# cactusCup_v2.net
KiCad netlist of a schematic drawn in EAGLE
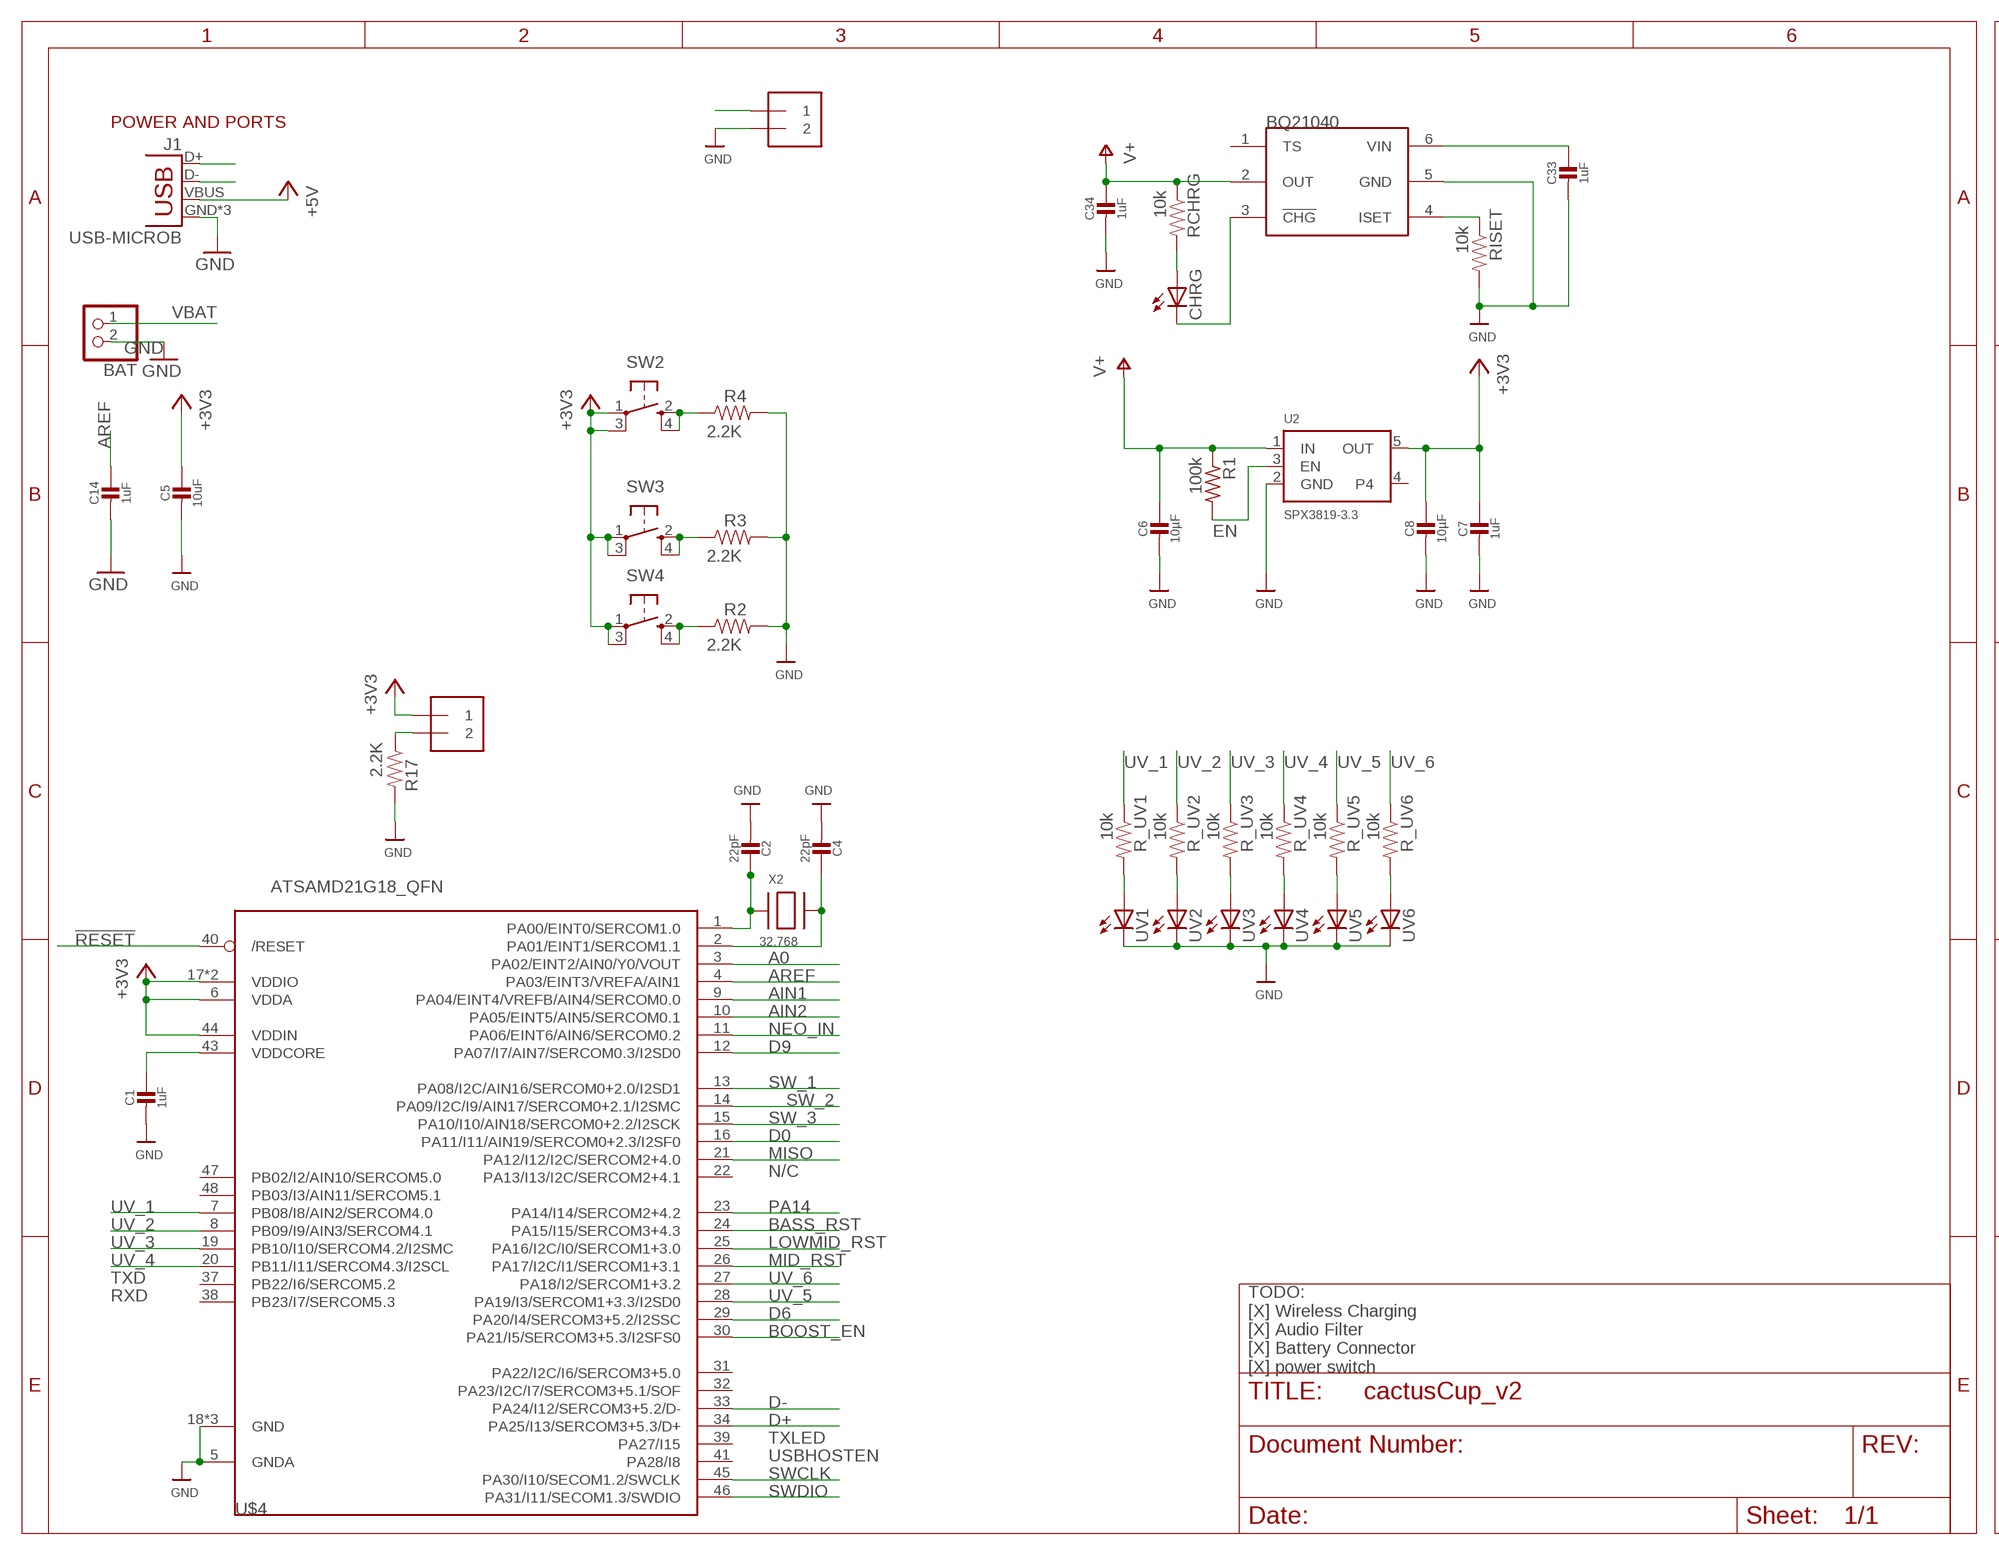
[diagram p0: schematic, sheet 1, part 1 of 2]
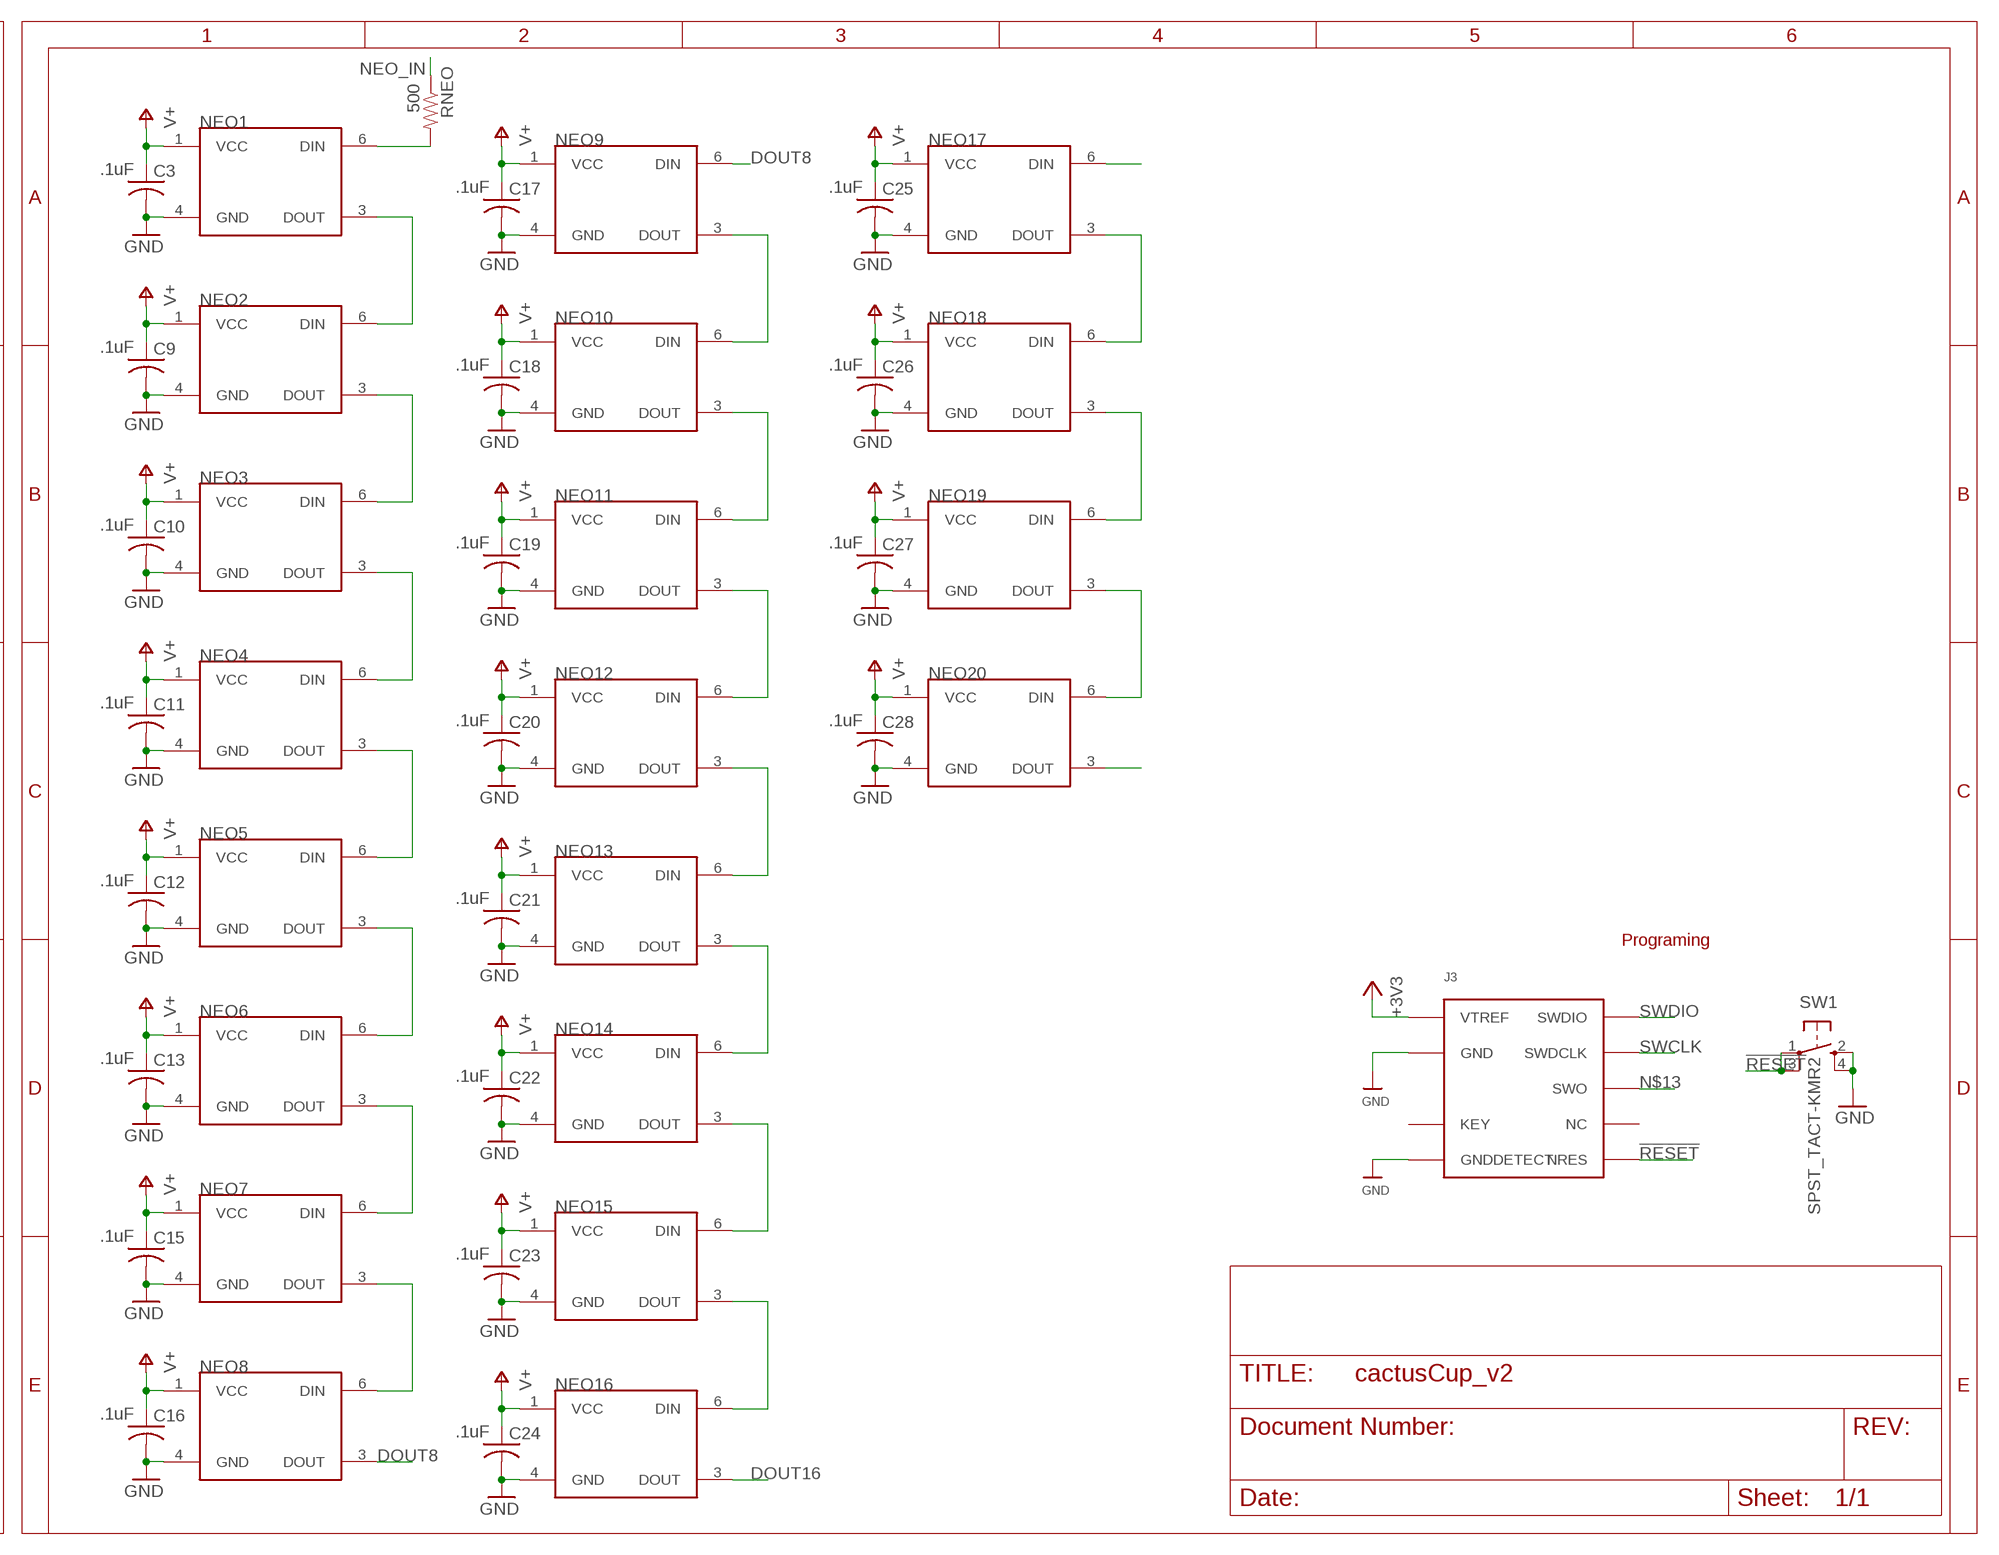
[diagram p1: schematic, sheet 1, part 2 of 2]

(export (version "E")
  (design (tool "Eeschema 10.0.6"))
  (components
    (comp (ref "BAT")
      (value "JST_2PIN-SMT-RA")
      (footprint "eagle-import:JST-PH-2-SMT-RA")
      (libsource (lib "eagle-import") (part "JST_2PIN-SMT-RA"))
    )
    (comp (ref "BQ21040")
      (value "BQ21040")
      (footprint "eagle-import:SOT23-6")
      (libsource (lib "eagle-import") (part "BQ21040"))
    )
    (comp (ref "C1")
      (value "1uF")
      (footprint "eagle-import:0603-NO")
      (libsource (lib "eagle-import") (part "CAP_CERAMIC0603_NO"))
    )
    (comp (ref "C2")
      (value "22pF")
      (footprint "eagle-import:0603-NO")
      (libsource (lib "eagle-import") (part "CAP_CERAMIC0603_NO"))
    )
    (comp (ref "C3")
      (value ".1uF")
      (footprint "eagle-import:C0603")
      (libsource (lib "eagle-import") (part "C-USC0603"))
    )
    (comp (ref "C4")
      (value "22pF")
      (footprint "eagle-import:0603-NO")
      (libsource (lib "eagle-import") (part "CAP_CERAMIC0603_NO"))
    )
    (comp (ref "C5")
      (value "10uF")
      (footprint "eagle-import:0805-NO")
      (libsource (lib "eagle-import") (part "CAP_CERAMIC0805-NOOUTLINE"))
    )
    (comp (ref "C6")
      (value "10µF")
      (footprint "eagle-import:0805-NO")
      (libsource (lib "eagle-import") (part "CAP_CERAMIC0805-NOOUTLINE"))
    )
    (comp (ref "C7")
      (value "1uF")
      (footprint "eagle-import:0603-NO")
      (libsource (lib "eagle-import") (part "CAP_CERAMIC0603_NO"))
    )
    (comp (ref "C8")
      (value "10µF")
      (footprint "eagle-import:0805-NO")
      (libsource (lib "eagle-import") (part "CAP_CERAMIC0805-NOOUTLINE"))
    )
    (comp (ref "C9")
      (value ".1uF")
      (footprint "eagle-import:C0603")
      (libsource (lib "eagle-import") (part "C-USC0603"))
    )
    (comp (ref "C10")
      (value ".1uF")
      (footprint "eagle-import:C0603")
      (libsource (lib "eagle-import") (part "C-USC0603"))
    )
    (comp (ref "C11")
      (value ".1uF")
      (footprint "eagle-import:C0603")
      (libsource (lib "eagle-import") (part "C-USC0603"))
    )
    (comp (ref "C12")
      (value ".1uF")
      (footprint "eagle-import:C0603")
      (libsource (lib "eagle-import") (part "C-USC0603"))
    )
    (comp (ref "C13")
      (value ".1uF")
      (footprint "eagle-import:C0603")
      (libsource (lib "eagle-import") (part "C-USC0603"))
    )
    (comp (ref "C14")
      (value "1uF")
      (footprint "eagle-import:0603-NO")
      (libsource (lib "eagle-import") (part "CAP_CERAMIC0603_NO"))
    )
    (comp (ref "C15")
      (value ".1uF")
      (footprint "eagle-import:C0603")
      (libsource (lib "eagle-import") (part "C-USC0603"))
    )
    (comp (ref "C16")
      (value ".1uF")
      (footprint "eagle-import:C0603")
      (libsource (lib "eagle-import") (part "C-USC0603"))
    )
    (comp (ref "C17")
      (value ".1uF")
      (footprint "eagle-import:C0603")
      (libsource (lib "eagle-import") (part "C-USC0603"))
    )
    (comp (ref "C18")
      (value ".1uF")
      (footprint "eagle-import:C0603")
      (libsource (lib "eagle-import") (part "C-USC0603"))
    )
    (comp (ref "C19")
      (value ".1uF")
      (footprint "eagle-import:C0603")
      (libsource (lib "eagle-import") (part "C-USC0603"))
    )
    (comp (ref "C20")
      (value ".1uF")
      (footprint "eagle-import:C0603")
      (libsource (lib "eagle-import") (part "C-USC0603"))
    )
    (comp (ref "C21")
      (value ".1uF")
      (footprint "eagle-import:C0603")
      (libsource (lib "eagle-import") (part "C-USC0603"))
    )
    (comp (ref "C22")
      (value ".1uF")
      (footprint "eagle-import:C0603")
      (libsource (lib "eagle-import") (part "C-USC0603"))
    )
    (comp (ref "C23")
      (value ".1uF")
      (footprint "eagle-import:C0603")
      (libsource (lib "eagle-import") (part "C-USC0603"))
    )
    (comp (ref "C24")
      (value ".1uF")
      (footprint "eagle-import:C0603")
      (libsource (lib "eagle-import") (part "C-USC0603"))
    )
    (comp (ref "C25")
      (value ".1uF")
      (footprint "eagle-import:C0603")
      (libsource (lib "eagle-import") (part "C-USC0603"))
    )
    (comp (ref "C26")
      (value ".1uF")
      (footprint "eagle-import:C0603")
      (libsource (lib "eagle-import") (part "C-USC0603"))
    )
    (comp (ref "C27")
      (value ".1uF")
      (footprint "eagle-import:C0603")
      (libsource (lib "eagle-import") (part "C-USC0603"))
    )
    (comp (ref "C28")
      (value ".1uF")
      (footprint "eagle-import:C0603")
      (libsource (lib "eagle-import") (part "C-USC0603"))
    )
    (comp (ref "C33")
      (value "1uF")
      (footprint "eagle-import:0603-NO")
      (libsource (lib "eagle-import") (part "CAP_CERAMIC0603_NO"))
    )
    (comp (ref "C34")
      (value "1uF")
      (footprint "eagle-import:0603-NO")
      (libsource (lib "eagle-import") (part "CAP_CERAMIC0603_NO"))
    )
    (comp (ref "CHRG")
      (value "LEDCHIPLED_0603")
      (footprint "eagle-import:CHIPLED_0603")
      (libsource (lib "eagle-import") (part "LEDCHIPLED_0603"))
    )
    (comp (ref "J1")
      (value "USB-MICROB")
      (footprint "eagle-import:USB-MICROB")
      (libsource (lib "eagle-import") (part "USB-MICROB"))
    )
    (comp (ref "J2")
      (value "1X2-3.5MM")
      (footprint "eagle-import:1X2-3.5MM")
      (libsource (lib "eagle-import") (part "1X2-3.5MM"))
    )
    (comp (ref "J3")
      (value "JLINK_10PIN")
      (footprint "eagle-import:FTSH-105-01-F-DH")
      (libsource (lib "eagle-import") (part "JLINK_10PIN"))
    )
    (comp (ref "J4")
      (value "1X2-3.5MM")
      (footprint "eagle-import:1X2-3.5MM")
      (libsource (lib "eagle-import") (part "1X2-3.5MM"))
    )
    (comp (ref "NEO1")
      (value "NEOPIXEL")
      (footprint "eagle-import:RGBLED5050")
      (libsource (lib "eagle-import") (part "NEOPIXEL"))
    )
    (comp (ref "NEO2")
      (value "NEOPIXEL")
      (footprint "eagle-import:RGBLED5050")
      (libsource (lib "eagle-import") (part "NEOPIXEL"))
    )
    (comp (ref "NEO3")
      (value "NEOPIXEL")
      (footprint "eagle-import:RGBLED5050")
      (libsource (lib "eagle-import") (part "NEOPIXEL"))
    )
    (comp (ref "NEO4")
      (value "NEOPIXEL")
      (footprint "eagle-import:RGBLED5050")
      (libsource (lib "eagle-import") (part "NEOPIXEL"))
    )
    (comp (ref "NEO5")
      (value "NEOPIXEL")
      (footprint "eagle-import:RGBLED5050")
      (libsource (lib "eagle-import") (part "NEOPIXEL"))
    )
    (comp (ref "NEO6")
      (value "NEOPIXEL")
      (footprint "eagle-import:RGBLED5050")
      (libsource (lib "eagle-import") (part "NEOPIXEL"))
    )
    (comp (ref "NEO7")
      (value "NEOPIXEL")
      (footprint "eagle-import:RGBLED5050")
      (libsource (lib "eagle-import") (part "NEOPIXEL"))
    )
    (comp (ref "NEO8")
      (value "NEOPIXEL")
      (footprint "eagle-import:RGBLED5050")
      (libsource (lib "eagle-import") (part "NEOPIXEL"))
    )
    (comp (ref "NEO9")
      (value "NEOPIXEL")
      (footprint "eagle-import:RGBLED5050")
      (libsource (lib "eagle-import") (part "NEOPIXEL"))
    )
    (comp (ref "NEO10")
      (value "NEOPIXEL")
      (footprint "eagle-import:RGBLED5050")
      (libsource (lib "eagle-import") (part "NEOPIXEL"))
    )
    (comp (ref "NEO11")
      (value "NEOPIXEL")
      (footprint "eagle-import:RGBLED5050")
      (libsource (lib "eagle-import") (part "NEOPIXEL"))
    )
    (comp (ref "NEO12")
      (value "NEOPIXEL")
      (footprint "eagle-import:RGBLED5050")
      (libsource (lib "eagle-import") (part "NEOPIXEL"))
    )
    (comp (ref "NEO13")
      (value "NEOPIXEL")
      (footprint "eagle-import:RGBLED5050")
      (libsource (lib "eagle-import") (part "NEOPIXEL"))
    )
    (comp (ref "NEO14")
      (value "NEOPIXEL")
      (footprint "eagle-import:RGBLED5050")
      (libsource (lib "eagle-import") (part "NEOPIXEL"))
    )
    (comp (ref "NEO15")
      (value "NEOPIXEL")
      (footprint "eagle-import:RGBLED5050")
      (libsource (lib "eagle-import") (part "NEOPIXEL"))
    )
    (comp (ref "NEO16")
      (value "NEOPIXEL")
      (footprint "eagle-import:RGBLED5050")
      (libsource (lib "eagle-import") (part "NEOPIXEL"))
    )
    (comp (ref "NEO17")
      (value "NEOPIXEL")
      (footprint "eagle-import:RGBLED5050")
      (libsource (lib "eagle-import") (part "NEOPIXEL"))
    )
    (comp (ref "NEO18")
      (value "NEOPIXEL")
      (footprint "eagle-import:RGBLED5050")
      (libsource (lib "eagle-import") (part "NEOPIXEL"))
    )
    (comp (ref "NEO19")
      (value "NEOPIXEL")
      (footprint "eagle-import:RGBLED5050")
      (libsource (lib "eagle-import") (part "NEOPIXEL"))
    )
    (comp (ref "NEO20")
      (value "NEOPIXEL")
      (footprint "eagle-import:RGBLED5050")
      (libsource (lib "eagle-import") (part "NEOPIXEL"))
    )
    (comp (ref "R1")
      (value "100k")
      (footprint "eagle-import:R0603")
      (libsource (lib "eagle-import") (part "R-US_R0603"))
    )
    (comp (ref "R2")
      (value "2.2K")
      (footprint "eagle-import:0603-RES")
      (libsource (lib "eagle-import") (part "0.27OHM-1/10W-1%(0603)"))
    )
    (comp (ref "R3")
      (value "2.2K")
      (footprint "eagle-import:0603-RES")
      (libsource (lib "eagle-import") (part "0.27OHM-1/10W-1%(0603)"))
    )
    (comp (ref "R4")
      (value "2.2K")
      (footprint "eagle-import:0603-RES")
      (libsource (lib "eagle-import") (part "0.27OHM-1/10W-1%(0603)"))
    )
    (comp (ref "R17")
      (value "2.2K")
      (footprint "eagle-import:0603-RES")
      (libsource (lib "eagle-import") (part "0.27OHM-1/10W-1%(0603)"))
    )
    (comp (ref "RCHRG")
      (value "10k")
      (footprint "eagle-import:0603-RES")
      (libsource (lib "eagle-import") (part "0.27OHM-1/10W-1%(0603)"))
    )
    (comp (ref "RISET")
      (value "10k")
      (footprint "eagle-import:0603-RES")
      (libsource (lib "eagle-import") (part "0.27OHM-1/10W-1%(0603)"))
    )
    (comp (ref "RNEO")
      (value "500")
      (footprint "eagle-import:0603-RES")
      (libsource (lib "eagle-import") (part "0.27OHM-1/10W-1%(0603)"))
    )
    (comp (ref "R_UV1")
      (value "10k")
      (footprint "eagle-import:0603-RES")
      (libsource (lib "eagle-import") (part "0.27OHM-1/10W-1%(0603)"))
    )
    (comp (ref "R_UV2")
      (value "10k")
      (footprint "eagle-import:0603-RES")
      (libsource (lib "eagle-import") (part "0.27OHM-1/10W-1%(0603)"))
    )
    (comp (ref "R_UV3")
      (value "10k")
      (footprint "eagle-import:0603-RES")
      (libsource (lib "eagle-import") (part "0.27OHM-1/10W-1%(0603)"))
    )
    (comp (ref "R_UV4")
      (value "10k")
      (footprint "eagle-import:0603-RES")
      (libsource (lib "eagle-import") (part "0.27OHM-1/10W-1%(0603)"))
    )
    (comp (ref "R_UV5")
      (value "10k")
      (footprint "eagle-import:0603-RES")
      (libsource (lib "eagle-import") (part "0.27OHM-1/10W-1%(0603)"))
    )
    (comp (ref "R_UV6")
      (value "10k")
      (footprint "eagle-import:0603-RES")
      (libsource (lib "eagle-import") (part "0.27OHM-1/10W-1%(0603)"))
    )
    (comp (ref "SW1")
      (value "SPST_TACT-KMR2")
      (footprint "eagle-import:KMR2")
      (libsource (lib "eagle-import") (part "SPST_TACT-KMR2"))
    )
    (comp (ref "SW2")
      (value "SPST_TACT-KMR2")
      (footprint "eagle-import:KMR2")
      (libsource (lib "eagle-import") (part "SPST_TACT-KMR2"))
    )
    (comp (ref "SW3")
      (value "SPST_TACT-KMR2")
      (footprint "eagle-import:KMR2")
      (libsource (lib "eagle-import") (part "SPST_TACT-KMR2"))
    )
    (comp (ref "SW4")
      (value "SPST_TACT-KMR2")
      (footprint "eagle-import:KMR2")
      (libsource (lib "eagle-import") (part "SPST_TACT-KMR2"))
    )
    (comp (ref "U$4")
      (value "ATSAMD21G18_QFN")
      (footprint "eagle-import:TQFP48")
      (libsource (lib "eagle-import") (part "ATSAMD21J"))
    )
    (comp (ref "U2")
      (value "SPX3819-3.3")
      (footprint "eagle-import:SOT23-5")
      (libsource (lib "eagle-import") (part "VREG_SOT23-5"))
    )
    (comp (ref "UV1")
      (value "LEDCHIPLED_0603")
      (footprint "eagle-import:CHIPLED_0603")
      (libsource (lib "eagle-import") (part "LEDCHIPLED_0603"))
    )
    (comp (ref "UV2")
      (value "LEDCHIPLED_0603")
      (footprint "eagle-import:CHIPLED_0603")
      (libsource (lib "eagle-import") (part "LEDCHIPLED_0603"))
    )
    (comp (ref "UV3")
      (value "LEDCHIPLED_0603")
      (footprint "eagle-import:CHIPLED_0603")
      (libsource (lib "eagle-import") (part "LEDCHIPLED_0603"))
    )
    (comp (ref "UV4")
      (value "LEDCHIPLED_0603")
      (footprint "eagle-import:CHIPLED_0603")
      (libsource (lib "eagle-import") (part "LEDCHIPLED_0603"))
    )
    (comp (ref "UV5")
      (value "LEDCHIPLED_0603")
      (footprint "eagle-import:CHIPLED_0603")
      (libsource (lib "eagle-import") (part "LEDCHIPLED_0603"))
    )
    (comp (ref "UV6")
      (value "LEDCHIPLED_0603")
      (footprint "eagle-import:CHIPLED_0603")
      (libsource (lib "eagle-import") (part "LEDCHIPLED_0603"))
    )
    (comp (ref "X2")
      (value "32.768")
      (footprint "eagle-import:XTAL3215")
      (libsource (lib "eagle-import") (part "XTAL-3.2X1.5"))
    )
  )
  (nets
    (net (code "1") (name "+3V3") (class "Default")
      (node (ref "C5") (pin "1") (pinfunction "1_1") (pintype "passive"))
      (node (ref "C7") (pin "1") (pinfunction "1_1") (pintype "passive"))
      (node (ref "C8") (pin "1") (pinfunction "1_1") (pintype "passive"))
      (node (ref "J2") (pin "1") (pinfunction "1_1") (pintype "passive"))
      (node (ref "J3") (pin "1") (pinfunction "VTREF_1") (pintype "bidirectional"))
      (node (ref "SW2") (pin "1") (pinfunction "P_1") (pintype "passive"))
      (node (ref "SW2") (pin "3") (pinfunction "P1_3") (pintype "passive"))
      (node (ref "SW3") (pin "1") (pinfunction "P_1") (pintype "passive"))
      (node (ref "SW3") (pin "3") (pinfunction "P1_3") (pintype "passive"))
      (node (ref "SW4") (pin "1") (pinfunction "P_1") (pintype "passive"))
      (node (ref "SW4") (pin "3") (pinfunction "P1_3") (pintype "passive"))
      (node (ref "U$4") (pin "17") (pinfunction "VDDIO_17") (pintype "power_in"))
      (node (ref "U$4") (pin "36") (pinfunction "VDDIO_36") (pintype "power_in"))
      (node (ref "U$4") (pin "44") (pinfunction "VDDIN_44") (pintype "power_in"))
      (node (ref "U$4") (pin "6") (pinfunction "VDDA_6") (pintype "power_in"))
      (node (ref "U2") (pin "5") (pinfunction "OUT_5") (pintype "power_in"))
    )
    (net (code "2") (name "+5V") (class "Default")
      (node (ref "J1") (pin "VBUS") (pinfunction "VBUS_VBUS") (pintype "bidirectional"))
    )
    (net (code "3") (name "/A0") (class "Default")
      (node (ref "U$4") (pin "3") (pinfunction "PA02/EINT2/AIN0/Y0/VOUT_3") (pintype "bidirectional"))
    )
    (net (code "4") (name "/AIN1") (class "Default")
      (node (ref "U$4") (pin "9") (pinfunction "PA04/EINT4/VREFB/AIN4/SERCOM0.0_9") (pintype "bidirectional"))
    )
    (net (code "5") (name "/AIN2") (class "Default")
      (node (ref "U$4") (pin "10") (pinfunction "PA05/EINT5/AIN5/SERCOM0.1_10") (pintype "bidirectional"))
    )
    (net (code "6") (name "/AREF") (class "Default")
      (node (ref "C14") (pin "1") (pinfunction "1_1") (pintype "passive"))
      (node (ref "U$4") (pin "4") (pinfunction "PA03/EINT3/VREFA/AIN1_4") (pintype "bidirectional"))
    )
    (net (code "7") (name "/BASS_RST") (class "Default")
      (node (ref "U$4") (pin "24") (pinfunction "PA15/I15/SERCOM3+4.3_24") (pintype "bidirectional"))
    )
    (net (code "8") (name "/BOOST_EN") (class "Default")
      (node (ref "U$4") (pin "30") (pinfunction "PA21/I5/SERCOM3+5.3/I2SFS0_30") (pintype "bidirectional"))
    )
    (net (code "9") (name "/D+") (class "Default")
      (node (ref "J1") (pin "D+") (pinfunction "D+_D+") (pintype "bidirectional"))
      (node (ref "U$4") (pin "34") (pinfunction "PA25/I13/SERCOM3+5.3/D+_34") (pintype "bidirectional"))
    )
    (net (code "10") (name "/D-") (class "Default")
      (node (ref "J1") (pin "D-") (pinfunction "D-_D-") (pintype "bidirectional"))
      (node (ref "U$4") (pin "33") (pinfunction "PA24/I12/SERCOM3+5.2/D-_33") (pintype "bidirectional"))
    )
    (net (code "11") (name "/D0") (class "Default")
      (node (ref "U$4") (pin "16") (pinfunction "PA11/I11/AIN19/SERCOM0+2.3/I2SF0_16") (pintype "bidirectional"))
    )
    (net (code "12") (name "/D6") (class "Default")
      (node (ref "J2") (pin "2") (pinfunction "2_2") (pintype "passive"))
      (node (ref "R17") (pin "1") (pinfunction "1_1") (pintype "passive"))
      (node (ref "U$4") (pin "29") (pinfunction "PA20/I4/SERCOM3+5.2/I2SSC_29") (pintype "bidirectional"))
    )
    (net (code "13") (name "/D9") (class "Default")
      (node (ref "U$4") (pin "12") (pinfunction "PA07/I7/AIN7/SERCOM0.3/I2SD0_12") (pintype "bidirectional"))
    )
    (net (code "14") (name "/DOUT8") (class "Default")
      (node (ref "NEO8") (pin "3") (pinfunction "DOUT_3") (pintype "bidirectional"))
      (node (ref "NEO9") (pin "6") (pinfunction "DIN_6") (pintype "bidirectional"))
    )
    (net (code "15") (name "/DOUT16") (class "Default")
      (node (ref "NEO16") (pin "3") (pinfunction "DOUT_3") (pintype "bidirectional"))
      (node (ref "NEO17") (pin "6") (pinfunction "DIN_6") (pintype "bidirectional"))
    )
    (net (code "16") (name "/EN") (class "Default")
      (node (ref "R1") (pin "2") (pinfunction "2_2") (pintype "passive"))
      (node (ref "U2") (pin "3") (pinfunction "EN_3") (pintype "input"))
    )
    (net (code "17") (name "/LOWMID_RST") (class "Default")
      (node (ref "U$4") (pin "25") (pinfunction "PA16/I2C/I0/SERCOM1+3.0_25") (pintype "bidirectional"))
    )
    (net (code "18") (name "/MID_RST") (class "Default")
      (node (ref "U$4") (pin "26") (pinfunction "PA17/I2C/I1/SERCOM1+3.1_26") (pintype "bidirectional"))
    )
    (net (code "19") (name "/MISO") (class "Default")
      (node (ref "U$4") (pin "21") (pinfunction "PA12/I12/I2C/SERCOM2+4.0_21") (pintype "bidirectional"))
    )
    (net (code "20") (name "/N$13") (class "Default")
      (node (ref "J3") (pin "6") (pinfunction "SWO_6") (pintype "bidirectional"))
    )
    (net (code "21") (name "/NEO_IN") (class "Default")
      (node (ref "RNEO") (pin "1") (pinfunction "1_1") (pintype "passive"))
      (node (ref "U$4") (pin "11") (pinfunction "PA06/EINT6/AIN6/SERCOM0.2_11") (pintype "bidirectional"))
    )
    (net (code "22") (name "/PA14") (class "Default")
      (node (ref "U$4") (pin "23") (pinfunction "PA14/I14/SERCOM2+4.2_23") (pintype "bidirectional"))
    )
    (net (code "23") (name "/SWCLK") (class "Default")
      (node (ref "J3") (pin "4") (pinfunction "SWDCLK_4") (pintype "bidirectional"))
      (node (ref "U$4") (pin "45") (pinfunction "PA30/I10/SECOM1.2/SWCLK_45") (pintype "bidirectional"))
    )
    (net (code "24") (name "/SWDIO") (class "Default")
      (node (ref "J3") (pin "2") (pinfunction "SWDIO_2") (pintype "bidirectional"))
      (node (ref "U$4") (pin "46") (pinfunction "PA31/I11/SECOM1.3/SWDIO_46") (pintype "bidirectional"))
    )
    (net (code "25") (name "/SW_1") (class "Default")
      (node (ref "R4") (pin "1") (pinfunction "1_1") (pintype "passive"))
      (node (ref "SW2") (pin "2") (pinfunction "S_2") (pintype "passive"))
      (node (ref "SW2") (pin "4") (pinfunction "S1_4") (pintype "passive"))
      (node (ref "U$4") (pin "13") (pinfunction "PA08/I2C/AIN16/SERCOM0+2.0/I2SD1_13") (pintype "bidirectional"))
    )
    (net (code "26") (name "/SW_2") (class "Default")
      (node (ref "R3") (pin "1") (pinfunction "1_1") (pintype "passive"))
      (node (ref "SW3") (pin "2") (pinfunction "S_2") (pintype "passive"))
      (node (ref "SW3") (pin "4") (pinfunction "S1_4") (pintype "passive"))
      (node (ref "U$4") (pin "14") (pinfunction "PA09/I2C/I9/AIN17/SERCOM0+2.1/I2SMC_14") (pintype "bidirectional"))
    )
    (net (code "27") (name "/SW_3") (class "Default")
      (node (ref "R2") (pin "1") (pinfunction "1_1") (pintype "passive"))
      (node (ref "SW4") (pin "2") (pinfunction "S_2") (pintype "passive"))
      (node (ref "SW4") (pin "4") (pinfunction "S1_4") (pintype "passive"))
      (node (ref "U$4") (pin "15") (pinfunction "PA10/I10/AIN18/SERCOM0+2.2/I2SCK_15") (pintype "bidirectional"))
    )
    (net (code "28") (name "/UV_1") (class "Default")
      (node (ref "R_UV1") (pin "1") (pinfunction "1_1") (pintype "passive"))
      (node (ref "U$4") (pin "7") (pinfunction "PB08/I8/AIN2/SERCOM4.0_7") (pintype "bidirectional"))
    )
    (net (code "29") (name "/UV_2") (class "Default")
      (node (ref "R_UV2") (pin "1") (pinfunction "1_1") (pintype "passive"))
      (node (ref "U$4") (pin "8") (pinfunction "PB09/I9/AIN3/SERCOM4.1_8") (pintype "bidirectional"))
    )
    (net (code "30") (name "/UV_3") (class "Default")
      (node (ref "R_UV3") (pin "1") (pinfunction "1_1") (pintype "passive"))
      (node (ref "U$4") (pin "19") (pinfunction "PB10/I10/SERCOM4.2/I2SMC_19") (pintype "bidirectional"))
    )
    (net (code "31") (name "/UV_4") (class "Default")
      (node (ref "R_UV4") (pin "1") (pinfunction "1_1") (pintype "passive"))
      (node (ref "U$4") (pin "20") (pinfunction "PB11/I11/SERCOM4.3/I2SCL_20") (pintype "bidirectional"))
    )
    (net (code "32") (name "/UV_5") (class "Default")
      (node (ref "R_UV5") (pin "1") (pinfunction "1_1") (pintype "passive"))
      (node (ref "U$4") (pin "28") (pinfunction "PA19/I3/SERCOM1+3.3/I2SD0_28") (pintype "bidirectional"))
    )
    (net (code "33") (name "/UV_6") (class "Default")
      (node (ref "R_UV6") (pin "1") (pinfunction "1_1") (pintype "passive"))
      (node (ref "U$4") (pin "27") (pinfunction "PA18/I2/SERCOM1+3.2_27") (pintype "bidirectional"))
    )
    (net (code "34") (name "/VBUS") (class "Default")
      (node (ref "BQ21040") (pin "6") (pinfunction "VIN_6") (pintype "bidirectional"))
      (node (ref "C33") (pin "1") (pinfunction "1_1") (pintype "passive"))
      (node (ref "J4") (pin "1") (pinfunction "1_1") (pintype "passive"))
    )
    (net (code "35") (name "/~{RESET}") (class "Default")
      (node (ref "J3") (pin "10") (pinfunction "NRES_10") (pintype "bidirectional"))
      (node (ref "SW1") (pin "1") (pinfunction "P_1") (pintype "passive"))
      (node (ref "SW1") (pin "3") (pinfunction "P1_3") (pintype "passive"))
      (node (ref "U$4") (pin "40") (pinfunction "/RESET_40") (pintype "bidirectional"))
    )
    (net (code "36") (name "GND") (class "Default")
      (node (ref "BAT") (pin "2") (pinfunction "1_2") (pintype "passive"))
      (node (ref "BQ21040") (pin "5") (pinfunction "GND_5") (pintype "bidirectional"))
      (node (ref "C1") (pin "2") (pinfunction "2_2") (pintype "passive"))
      (node (ref "C10") (pin "2") (pinfunction "2_2") (pintype "passive"))
      (node (ref "C11") (pin "2") (pinfunction "2_2") (pintype "passive"))
      (node (ref "C12") (pin "2") (pinfunction "2_2") (pintype "passive"))
      (node (ref "C13") (pin "2") (pinfunction "2_2") (pintype "passive"))
      (node (ref "C14") (pin "2") (pinfunction "2_2") (pintype "passive"))
      (node (ref "C15") (pin "2") (pinfunction "2_2") (pintype "passive"))
      (node (ref "C16") (pin "2") (pinfunction "2_2") (pintype "passive"))
      (node (ref "C17") (pin "2") (pinfunction "2_2") (pintype "passive"))
      (node (ref "C18") (pin "2") (pinfunction "2_2") (pintype "passive"))
      (node (ref "C19") (pin "2") (pinfunction "2_2") (pintype "passive"))
      (node (ref "C2") (pin "2") (pinfunction "2_2") (pintype "passive"))
      (node (ref "C20") (pin "2") (pinfunction "2_2") (pintype "passive"))
      (node (ref "C21") (pin "2") (pinfunction "2_2") (pintype "passive"))
      (node (ref "C22") (pin "2") (pinfunction "2_2") (pintype "passive"))
      (node (ref "C23") (pin "2") (pinfunction "2_2") (pintype "passive"))
      (node (ref "C24") (pin "2") (pinfunction "2_2") (pintype "passive"))
      (node (ref "C25") (pin "2") (pinfunction "2_2") (pintype "passive"))
      (node (ref "C26") (pin "2") (pinfunction "2_2") (pintype "passive"))
      (node (ref "C27") (pin "2") (pinfunction "2_2") (pintype "passive"))
      (node (ref "C28") (pin "2") (pinfunction "2_2") (pintype "passive"))
      (node (ref "C3") (pin "2") (pinfunction "2_2") (pintype "passive"))
      (node (ref "C33") (pin "2") (pinfunction "2_2") (pintype "passive"))
      (node (ref "C34") (pin "2") (pinfunction "2_2") (pintype "passive"))
      (node (ref "C4") (pin "2") (pinfunction "2_2") (pintype "passive"))
      (node (ref "C5") (pin "2") (pinfunction "2_2") (pintype "passive"))
      (node (ref "C6") (pin "2") (pinfunction "2_2") (pintype "passive"))
      (node (ref "C7") (pin "2") (pinfunction "2_2") (pintype "passive"))
      (node (ref "C8") (pin "2") (pinfunction "2_2") (pintype "passive"))
      (node (ref "C9") (pin "2") (pinfunction "2_2") (pintype "passive"))
      (node (ref "J1") (pin "GND") (pinfunction "GND_GND") (pintype "bidirectional"))
      (node (ref "J1") (pin "MT1") (pinfunction "GND_MT1") (pintype "bidirectional"))
      (node (ref "J1") (pin "MT2") (pinfunction "GND_MT2") (pintype "bidirectional"))
      (node (ref "J3") (pin "3") (pinfunction "GND_3") (pintype "bidirectional"))
      (node (ref "J3") (pin "5") (pinfunction "GND_5") (pintype "bidirectional"))
      (node (ref "J3") (pin "9") (pinfunction "GNDDETECT_9") (pintype "bidirectional"))
      (node (ref "J4") (pin "2") (pinfunction "2_2") (pintype "passive"))
      (node (ref "NEO1") (pin "4") (pinfunction "GND_4") (pintype "bidirectional"))
      (node (ref "NEO10") (pin "4") (pinfunction "GND_4") (pintype "bidirectional"))
      (node (ref "NEO11") (pin "4") (pinfunction "GND_4") (pintype "bidirectional"))
      (node (ref "NEO12") (pin "4") (pinfunction "GND_4") (pintype "bidirectional"))
      (node (ref "NEO13") (pin "4") (pinfunction "GND_4") (pintype "bidirectional"))
      (node (ref "NEO14") (pin "4") (pinfunction "GND_4") (pintype "bidirectional"))
      (node (ref "NEO15") (pin "4") (pinfunction "GND_4") (pintype "bidirectional"))
      (node (ref "NEO16") (pin "4") (pinfunction "GND_4") (pintype "bidirectional"))
      (node (ref "NEO17") (pin "4") (pinfunction "GND_4") (pintype "bidirectional"))
      (node (ref "NEO18") (pin "4") (pinfunction "GND_4") (pintype "bidirectional"))
      (node (ref "NEO19") (pin "4") (pinfunction "GND_4") (pintype "bidirectional"))
      (node (ref "NEO2") (pin "4") (pinfunction "GND_4") (pintype "bidirectional"))
      (node (ref "NEO20") (pin "4") (pinfunction "GND_4") (pintype "bidirectional"))
      (node (ref "NEO3") (pin "4") (pinfunction "GND_4") (pintype "bidirectional"))
      (node (ref "NEO4") (pin "4") (pinfunction "GND_4") (pintype "bidirectional"))
      (node (ref "NEO5") (pin "4") (pinfunction "GND_4") (pintype "bidirectional"))
      (node (ref "NEO6") (pin "4") (pinfunction "GND_4") (pintype "bidirectional"))
      (node (ref "NEO7") (pin "4") (pinfunction "GND_4") (pintype "bidirectional"))
      (node (ref "NEO8") (pin "4") (pinfunction "GND_4") (pintype "bidirectional"))
      (node (ref "NEO9") (pin "4") (pinfunction "GND_4") (pintype "bidirectional"))
      (node (ref "R17") (pin "2") (pinfunction "2_2") (pintype "passive"))
      (node (ref "R2") (pin "2") (pinfunction "2_2") (pintype "passive"))
      (node (ref "R3") (pin "2") (pinfunction "2_2") (pintype "passive"))
      (node (ref "R4") (pin "2") (pinfunction "2_2") (pintype "passive"))
      (node (ref "RISET") (pin "2") (pinfunction "2_2") (pintype "passive"))
      (node (ref "SW1") (pin "2") (pinfunction "S_2") (pintype "passive"))
      (node (ref "SW1") (pin "4") (pinfunction "S1_4") (pintype "passive"))
      (node (ref "U$4") (pin "18") (pinfunction "GND_18") (pintype "power_in"))
      (node (ref "U$4") (pin "35") (pinfunction "GND_35") (pintype "power_in"))
      (node (ref "U$4") (pin "42") (pinfunction "GND_42") (pintype "power_in"))
      (node (ref "U$4") (pin "5") (pinfunction "GNDA_5") (pintype "power_in"))
      (node (ref "U2") (pin "2") (pinfunction "GND_2") (pintype "power_in"))
      (node (ref "UV1") (pin "C") (pinfunction "C_C") (pintype "passive"))
      (node (ref "UV2") (pin "C") (pinfunction "C_C") (pintype "passive"))
      (node (ref "UV3") (pin "C") (pinfunction "C_C") (pintype "passive"))
      (node (ref "UV4") (pin "C") (pinfunction "C_C") (pintype "passive"))
      (node (ref "UV5") (pin "C") (pinfunction "C_C") (pintype "passive"))
      (node (ref "UV6") (pin "C") (pinfunction "C_C") (pintype "passive"))
    )
    (net (code "37") (name "Net-(BQ21040-ISET)") (class "Default")
      (node (ref "BQ21040") (pin "4") (pinfunction "ISET_4") (pintype "bidirectional"))
      (node (ref "RISET") (pin "1") (pinfunction "1_1") (pintype "passive"))
    )
    (net (code "38") (name "Net-(BQ21040-~{CHG})") (class "Default")
      (node (ref "BQ21040") (pin "3") (pinfunction "~{CHG}_3") (pintype "bidirectional"))
      (node (ref "CHRG") (pin "C") (pinfunction "C_C") (pintype "passive"))
    )
    (net (code "39") (name "Net-(CHRG-PadA)") (class "Default")
      (node (ref "CHRG") (pin "A") (pinfunction "A_A") (pintype "passive"))
      (node (ref "RCHRG") (pin "2") (pinfunction "2_2") (pintype "passive"))
    )
    (net (code "40") (name "Net-(NEO1-DIN)") (class "Default")
      (node (ref "NEO1") (pin "6") (pinfunction "DIN_6") (pintype "bidirectional"))
      (node (ref "RNEO") (pin "2") (pinfunction "2_2") (pintype "passive"))
    )
    (net (code "41") (name "Net-(NEO1-DOUT)") (class "Default")
      (node (ref "NEO1") (pin "3") (pinfunction "DOUT_3") (pintype "bidirectional"))
      (node (ref "NEO2") (pin "6") (pinfunction "DIN_6") (pintype "bidirectional"))
    )
    (net (code "42") (name "Net-(NEO2-DOUT)") (class "Default")
      (node (ref "NEO2") (pin "3") (pinfunction "DOUT_3") (pintype "bidirectional"))
      (node (ref "NEO3") (pin "6") (pinfunction "DIN_6") (pintype "bidirectional"))
    )
    (net (code "43") (name "Net-(NEO3-DOUT)") (class "Default")
      (node (ref "NEO3") (pin "3") (pinfunction "DOUT_3") (pintype "bidirectional"))
      (node (ref "NEO4") (pin "6") (pinfunction "DIN_6") (pintype "bidirectional"))
    )
    (net (code "44") (name "Net-(NEO4-DOUT)") (class "Default")
      (node (ref "NEO4") (pin "3") (pinfunction "DOUT_3") (pintype "bidirectional"))
      (node (ref "NEO5") (pin "6") (pinfunction "DIN_6") (pintype "bidirectional"))
    )
    (net (code "45") (name "Net-(NEO5-DOUT)") (class "Default")
      (node (ref "NEO5") (pin "3") (pinfunction "DOUT_3") (pintype "bidirectional"))
      (node (ref "NEO6") (pin "6") (pinfunction "DIN_6") (pintype "bidirectional"))
    )
    (net (code "46") (name "Net-(NEO6-DOUT)") (class "Default")
      (node (ref "NEO6") (pin "3") (pinfunction "DOUT_3") (pintype "bidirectional"))
      (node (ref "NEO7") (pin "6") (pinfunction "DIN_6") (pintype "bidirectional"))
    )
    (net (code "47") (name "Net-(NEO7-DOUT)") (class "Default")
      (node (ref "NEO7") (pin "3") (pinfunction "DOUT_3") (pintype "bidirectional"))
      (node (ref "NEO8") (pin "6") (pinfunction "DIN_6") (pintype "bidirectional"))
    )
    (net (code "48") (name "Net-(NEO10-DIN)") (class "Default")
      (node (ref "NEO10") (pin "6") (pinfunction "DIN_6") (pintype "bidirectional"))
      (node (ref "NEO9") (pin "3") (pinfunction "DOUT_3") (pintype "bidirectional"))
    )
    (net (code "49") (name "Net-(NEO10-DOUT)") (class "Default")
      (node (ref "NEO10") (pin "3") (pinfunction "DOUT_3") (pintype "bidirectional"))
      (node (ref "NEO11") (pin "6") (pinfunction "DIN_6") (pintype "bidirectional"))
    )
    (net (code "50") (name "Net-(NEO11-DOUT)") (class "Default")
      (node (ref "NEO11") (pin "3") (pinfunction "DOUT_3") (pintype "bidirectional"))
      (node (ref "NEO12") (pin "6") (pinfunction "DIN_6") (pintype "bidirectional"))
    )
    (net (code "51") (name "Net-(NEO12-DOUT)") (class "Default")
      (node (ref "NEO12") (pin "3") (pinfunction "DOUT_3") (pintype "bidirectional"))
      (node (ref "NEO13") (pin "6") (pinfunction "DIN_6") (pintype "bidirectional"))
    )
    (net (code "52") (name "Net-(NEO13-DOUT)") (class "Default")
      (node (ref "NEO13") (pin "3") (pinfunction "DOUT_3") (pintype "bidirectional"))
      (node (ref "NEO14") (pin "6") (pinfunction "DIN_6") (pintype "bidirectional"))
    )
    (net (code "53") (name "Net-(NEO14-DOUT)") (class "Default")
      (node (ref "NEO14") (pin "3") (pinfunction "DOUT_3") (pintype "bidirectional"))
      (node (ref "NEO15") (pin "6") (pinfunction "DIN_6") (pintype "bidirectional"))
    )
    (net (code "54") (name "Net-(NEO15-DOUT)") (class "Default")
      (node (ref "NEO15") (pin "3") (pinfunction "DOUT_3") (pintype "bidirectional"))
      (node (ref "NEO16") (pin "6") (pinfunction "DIN_6") (pintype "bidirectional"))
    )
    (net (code "55") (name "Net-(NEO17-DOUT)") (class "Default")
      (node (ref "NEO17") (pin "3") (pinfunction "DOUT_3") (pintype "bidirectional"))
      (node (ref "NEO18") (pin "6") (pinfunction "DIN_6") (pintype "bidirectional"))
    )
    (net (code "56") (name "Net-(NEO18-DOUT)") (class "Default")
      (node (ref "NEO18") (pin "3") (pinfunction "DOUT_3") (pintype "bidirectional"))
      (node (ref "NEO19") (pin "6") (pinfunction "DIN_6") (pintype "bidirectional"))
    )
    (net (code "57") (name "Net-(NEO19-DOUT)") (class "Default")
      (node (ref "NEO19") (pin "3") (pinfunction "DOUT_3") (pintype "bidirectional"))
      (node (ref "NEO20") (pin "6") (pinfunction "DIN_6") (pintype "bidirectional"))
    )
    (net (code "58") (name "Net-(R_UV1-Pad2)") (class "Default")
      (node (ref "R_UV1") (pin "2") (pinfunction "2_2") (pintype "passive"))
      (node (ref "UV1") (pin "A") (pinfunction "A_A") (pintype "passive"))
    )
    (net (code "59") (name "Net-(R_UV2-Pad2)") (class "Default")
      (node (ref "R_UV2") (pin "2") (pinfunction "2_2") (pintype "passive"))
      (node (ref "UV2") (pin "A") (pinfunction "A_A") (pintype "passive"))
    )
    (net (code "60") (name "Net-(R_UV3-Pad2)") (class "Default")
      (node (ref "R_UV3") (pin "2") (pinfunction "2_2") (pintype "passive"))
      (node (ref "UV3") (pin "A") (pinfunction "A_A") (pintype "passive"))
    )
    (net (code "61") (name "Net-(R_UV4-Pad2)") (class "Default")
      (node (ref "R_UV4") (pin "2") (pinfunction "2_2") (pintype "passive"))
      (node (ref "UV4") (pin "A") (pinfunction "A_A") (pintype "passive"))
    )
    (net (code "62") (name "Net-(R_UV5-Pad2)") (class "Default")
      (node (ref "R_UV5") (pin "2") (pinfunction "2_2") (pintype "passive"))
      (node (ref "UV5") (pin "A") (pinfunction "A_A") (pintype "passive"))
    )
    (net (code "63") (name "Net-(R_UV6-Pad2)") (class "Default")
      (node (ref "R_UV6") (pin "2") (pinfunction "2_2") (pintype "passive"))
      (node (ref "UV6") (pin "A") (pinfunction "A_A") (pintype "passive"))
    )
    (net (code "64") (name "Net-(U$4-PA00{slash}EINT0{slash}SERCOM1.0)") (class "Default")
      (node (ref "C2") (pin "1") (pinfunction "1_1") (pintype "passive"))
      (node (ref "U$4") (pin "1") (pinfunction "PA00/EINT0/SERCOM1.0_1") (pintype "bidirectional"))
      (node (ref "X2") (pin "P$1") (pinfunction "P$1_P$1") (pintype "bidirectional"))
    )
    (net (code "65") (name "Net-(U$4-PA01{slash}EINT1{slash}SERCOM1.1)") (class "Default")
      (node (ref "C4") (pin "1") (pinfunction "1_1") (pintype "passive"))
      (node (ref "U$4") (pin "2") (pinfunction "PA01/EINT1/SERCOM1.1_2") (pintype "bidirectional"))
      (node (ref "X2") (pin "P$2") (pinfunction "P$2_P$2") (pintype "bidirectional"))
    )
    (net (code "66") (name "Net-(U$4-VDDCORE)") (class "Default")
      (node (ref "C1") (pin "1") (pinfunction "1_1") (pintype "passive"))
      (node (ref "U$4") (pin "43") (pinfunction "VDDCORE_43") (pintype "power_in"))
    )
    (net (code "67") (name "V+") (class "Default")
      (node (ref "BAT") (pin "1") (pinfunction "2_1") (pintype "passive"))
      (node (ref "BQ21040") (pin "2") (pinfunction "OUT_2") (pintype "bidirectional"))
      (node (ref "C10") (pin "1") (pinfunction "1_1") (pintype "passive"))
      (node (ref "C11") (pin "1") (pinfunction "1_1") (pintype "passive"))
      (node (ref "C12") (pin "1") (pinfunction "1_1") (pintype "passive"))
      (node (ref "C13") (pin "1") (pinfunction "1_1") (pintype "passive"))
      (node (ref "C15") (pin "1") (pinfunction "1_1") (pintype "passive"))
      (node (ref "C16") (pin "1") (pinfunction "1_1") (pintype "passive"))
      (node (ref "C17") (pin "1") (pinfunction "1_1") (pintype "passive"))
      (node (ref "C18") (pin "1") (pinfunction "1_1") (pintype "passive"))
      (node (ref "C19") (pin "1") (pinfunction "1_1") (pintype "passive"))
      (node (ref "C20") (pin "1") (pinfunction "1_1") (pintype "passive"))
      (node (ref "C21") (pin "1") (pinfunction "1_1") (pintype "passive"))
      (node (ref "C22") (pin "1") (pinfunction "1_1") (pintype "passive"))
      (node (ref "C23") (pin "1") (pinfunction "1_1") (pintype "passive"))
      (node (ref "C24") (pin "1") (pinfunction "1_1") (pintype "passive"))
      (node (ref "C25") (pin "1") (pinfunction "1_1") (pintype "passive"))
      (node (ref "C26") (pin "1") (pinfunction "1_1") (pintype "passive"))
      (node (ref "C27") (pin "1") (pinfunction "1_1") (pintype "passive"))
      (node (ref "C28") (pin "1") (pinfunction "1_1") (pintype "passive"))
      (node (ref "C3") (pin "1") (pinfunction "1_1") (pintype "passive"))
      (node (ref "C34") (pin "1") (pinfunction "1_1") (pintype "passive"))
      (node (ref "C6") (pin "1") (pinfunction "1_1") (pintype "passive"))
      (node (ref "C9") (pin "1") (pinfunction "1_1") (pintype "passive"))
      (node (ref "NEO1") (pin "1") (pinfunction "VCC_1") (pintype "bidirectional"))
      (node (ref "NEO10") (pin "1") (pinfunction "VCC_1") (pintype "bidirectional"))
      (node (ref "NEO11") (pin "1") (pinfunction "VCC_1") (pintype "bidirectional"))
      (node (ref "NEO12") (pin "1") (pinfunction "VCC_1") (pintype "bidirectional"))
      (node (ref "NEO13") (pin "1") (pinfunction "VCC_1") (pintype "bidirectional"))
      (node (ref "NEO14") (pin "1") (pinfunction "VCC_1") (pintype "bidirectional"))
      (node (ref "NEO15") (pin "1") (pinfunction "VCC_1") (pintype "bidirectional"))
      (node (ref "NEO16") (pin "1") (pinfunction "VCC_1") (pintype "bidirectional"))
      (node (ref "NEO17") (pin "1") (pinfunction "VCC_1") (pintype "bidirectional"))
      (node (ref "NEO18") (pin "1") (pinfunction "VCC_1") (pintype "bidirectional"))
      (node (ref "NEO19") (pin "1") (pinfunction "VCC_1") (pintype "bidirectional"))
      (node (ref "NEO2") (pin "1") (pinfunction "VCC_1") (pintype "bidirectional"))
      (node (ref "NEO20") (pin "1") (pinfunction "VCC_1") (pintype "bidirectional"))
      (node (ref "NEO3") (pin "1") (pinfunction "VCC_1") (pintype "bidirectional"))
      (node (ref "NEO4") (pin "1") (pinfunction "VCC_1") (pintype "bidirectional"))
      (node (ref "NEO5") (pin "1") (pinfunction "VCC_1") (pintype "bidirectional"))
      (node (ref "NEO6") (pin "1") (pinfunction "VCC_1") (pintype "bidirectional"))
      (node (ref "NEO7") (pin "1") (pinfunction "VCC_1") (pintype "bidirectional"))
      (node (ref "NEO8") (pin "1") (pinfunction "VCC_1") (pintype "bidirectional"))
      (node (ref "NEO9") (pin "1") (pinfunction "VCC_1") (pintype "bidirectional"))
      (node (ref "R1") (pin "1") (pinfunction "1_1") (pintype "passive"))
      (node (ref "RCHRG") (pin "1") (pinfunction "1_1") (pintype "passive"))
      (node (ref "U2") (pin "1") (pinfunction "IN_1") (pintype "power_in"))
    )
    (net (code "68") (name "unconnected-(BQ21040-TS-Pad1)") (class "Default")
      (node (ref "BQ21040") (pin "1") (pinfunction "TS_1") (pintype "bidirectional"))
    )
    (net (code "69") (name "unconnected-(J3-KEY-Pad7)") (class "Default")
      (node (ref "J3") (pin "7") (pinfunction "KEY_7") (pintype "bidirectional"))
    )
    (net (code "70") (name "unconnected-(J3-NC-Pad8)") (class "Default")
      (node (ref "J3") (pin "8") (pinfunction "NC_8") (pintype "bidirectional"))
    )
    (net (code "71") (name "unconnected-(NEO20-DOUT-Pad3)") (class "Default")
      (node (ref "NEO20") (pin "3") (pinfunction "DOUT_3") (pintype "bidirectional"))
    )
    (net (code "72") (name "unconnected-(U$4-PA13{slash}I13{slash}I2C{slash}SERCOM2+4.1-Pad22)") (class "Default")
      (node (ref "U$4") (pin "22") (pinfunction "PA13/I13/I2C/SERCOM2+4.1_22") (pintype "bidirectional"))
    )
    (net (code "73") (name "unconnected-(U$4-PA22{slash}I2C{slash}I6{slash}SERCOM3+5.0-Pad31)") (class "Default")
      (node (ref "U$4") (pin "31") (pinfunction "PA22/I2C/I6/SERCOM3+5.0_31") (pintype "bidirectional"))
    )
    (net (code "74") (name "unconnected-(U$4-PA23{slash}I2C{slash}I7{slash}SERCOM3+5.1{slash}SOF-Pad32)") (class "Default")
      (node (ref "U$4") (pin "32") (pinfunction "PA23/I2C/I7/SERCOM3+5.1/SOF_32") (pintype "bidirectional"))
    )
    (net (code "75") (name "unconnected-(U$4-PA27{slash}I15-Pad39)") (class "Default")
      (node (ref "U$4") (pin "39") (pinfunction "PA27/I15_39") (pintype "bidirectional"))
    )
    (net (code "76") (name "unconnected-(U$4-PA28{slash}I8-Pad41)") (class "Default")
      (node (ref "U$4") (pin "41") (pinfunction "PA28/I8_41") (pintype "bidirectional"))
    )
    (net (code "77") (name "unconnected-(U$4-PB02{slash}I2{slash}AIN10{slash}SERCOM5.0-Pad47)") (class "Default")
      (node (ref "U$4") (pin "47") (pinfunction "PB02/I2/AIN10/SERCOM5.0_47") (pintype "bidirectional"))
    )
    (net (code "78") (name "unconnected-(U$4-PB03{slash}I3{slash}AIN11{slash}SERCOM5.1-Pad48)") (class "Default")
      (node (ref "U$4") (pin "48") (pinfunction "PB03/I3/AIN11/SERCOM5.1_48") (pintype "bidirectional"))
    )
    (net (code "79") (name "unconnected-(U$4-PB22{slash}I6{slash}SERCOM5.2-Pad37)") (class "Default")
      (node (ref "U$4") (pin "37") (pinfunction "PB22/I6/SERCOM5.2_37") (pintype "bidirectional"))
    )
    (net (code "80") (name "unconnected-(U$4-PB23{slash}I7{slash}SERCOM5.3-Pad38)") (class "Default")
      (node (ref "U$4") (pin "38") (pinfunction "PB23/I7/SERCOM5.3_38") (pintype "bidirectional"))
    )
    (net (code "81") (name "unconnected-(U2-P4-Pad4)") (class "Default")
      (node (ref "U2") (pin "4") (pinfunction "P4_4") (pintype "bidirectional"))
    )
  )
)
